# moto.net
KiCad netlist of a schematic drawn in Altium Designer
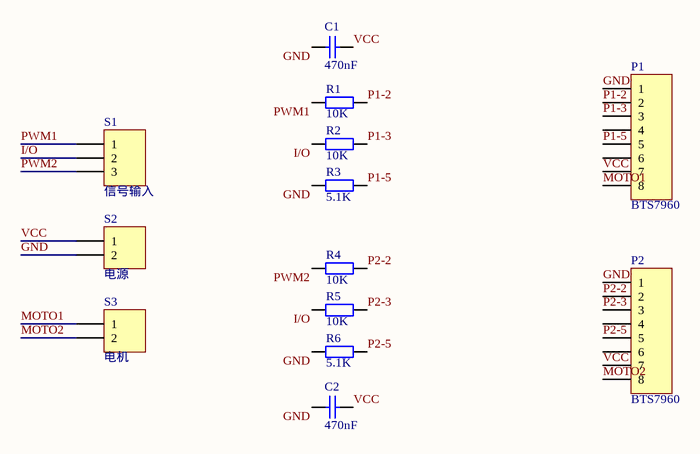
[diagram p0: moto.SchDoc]

(export (version "E")
  (design (tool "Eeschema 10.0.6"))
  (components
    (comp (ref "C1")
      (value "470nF")
      (footprint "0805")
      (description "Capacitor")
      (fields (field (name "PUBLISHER") "Altium Limited"))
      (libsource (lib "Miscellaneous Devices") (part "Cap"))
    )
    (comp (ref "C2")
      (value "470nF")
      (footprint "0805")
      (description "Capacitor")
      (fields (field (name "PUBLISHER") "Altium Limited"))
      (libsource (lib "Miscellaneous Devices") (part "Cap"))
    )
    (comp (ref "P1")
      (value "BTS7960")
      (footprint "BTS7970B")
      (description "Header, 8-Pin")
      (fields (field (name "PUBLISHER") "Altium Limited"))
      (libsource (lib "Miscellaneous Connectors") (part "Header 8"))
    )
    (comp (ref "P2")
      (value "BTS7960")
      (footprint "BTS7970B")
      (description "Header, 8-Pin")
      (fields (field (name "PUBLISHER") "Altium Limited"))
      (libsource (lib "Miscellaneous Connectors") (part "Header 8"))
    )
    (comp (ref "R1")
      (value "10K")
      (footprint "0805")
      (description "Resistor")
      (fields (field (name "PUBLISHER") "Altium Limited"))
      (libsource (lib "Miscellaneous Devices") (part "Res2"))
    )
    (comp (ref "R2")
      (value "10K")
      (footprint "0805")
      (description "Resistor")
      (fields (field (name "PUBLISHER") "Altium Limited"))
      (libsource (lib "") (part "Res2_1"))
    )
    (comp (ref "R3")
      (value "5.1K")
      (footprint "0805")
      (description "Resistor")
      (fields (field (name "PUBLISHER") "Altium Limited"))
      (libsource (lib "") (part "Res2_1"))
    )
    (comp (ref "R4")
      (value "10K")
      (footprint "0805")
      (description "Resistor")
      (fields (field (name "PUBLISHER") "Altium Limited"))
      (libsource (lib "Miscellaneous Devices") (part "Res2"))
    )
    (comp (ref "R5")
      (value "10K")
      (footprint "0805")
      (description "Resistor")
      (fields (field (name "PUBLISHER") "Altium Limited"))
      (libsource (lib "") (part "Res2_1"))
    )
    (comp (ref "R6")
      (value "5.1K")
      (footprint "0805")
      (description "Resistor")
      (fields (field (name "PUBLISHER") "Altium Limited"))
      (libsource (lib "") (part "Res2_1"))
    )
    (comp (ref "S1")
      (value "信号输入")
      (footprint "HDR1X3")
      (description "Header, 3-Pin")
      (fields (field (name "PUBLISHER") "Altium Limited"))
      (libsource (lib "Miscellaneous Connectors") (part "Header 3"))
    )
    (comp (ref "S2")
      (value "电源")
      (footprint "tongzhu")
      (description "Header, 2-Pin")
      (fields (field (name "PUBLISHER") "Altium Limited"))
      (libsource (lib "Miscellaneous Connectors") (part "Header 2"))
    )
    (comp (ref "S3")
      (value "电机")
      (footprint "tongzhu")
      (description "Header, 2-Pin")
      (fields (field (name "PUBLISHER") "Altium Limited"))
      (libsource (lib "Miscellaneous Connectors") (part "Header 2"))
    )
  )
  (nets
    (net (code "1") (name "/GND") (class "Default")
      (node (ref "C1") (pin "1") (pinfunction "1_1") (pintype "passive"))
      (node (ref "C2") (pin "1") (pinfunction "1_1") (pintype "passive"))
      (node (ref "P1") (pin "1") (pinfunction "1_1") (pintype "passive"))
      (node (ref "P2") (pin "1") (pinfunction "1_1") (pintype "passive"))
      (node (ref "R3") (pin "2") (pinfunction "2_2") (pintype "passive"))
      (node (ref "R6") (pin "2") (pinfunction "2_2") (pintype "passive"))
      (node (ref "S2") (pin "2") (pinfunction "2_2") (pintype "passive"))
    )
    (net (code "2") (name "/I{slash}O") (class "Default")
      (node (ref "R2") (pin "2") (pinfunction "2_2") (pintype "passive"))
      (node (ref "R5") (pin "2") (pinfunction "2_2") (pintype "passive"))
      (node (ref "S1") (pin "2") (pinfunction "2_2") (pintype "passive"))
    )
    (net (code "3") (name "/MOTO1") (class "Default")
      (node (ref "P1") (pin "8") (pinfunction "8_8") (pintype "passive"))
      (node (ref "S3") (pin "1") (pinfunction "1_1") (pintype "passive"))
    )
    (net (code "4") (name "/MOTO2") (class "Default")
      (node (ref "P2") (pin "8") (pinfunction "8_8") (pintype "passive"))
      (node (ref "S3") (pin "2") (pinfunction "2_2") (pintype "passive"))
    )
    (net (code "5") (name "/P1-2") (class "Default")
      (node (ref "P1") (pin "2") (pinfunction "2_2") (pintype "passive"))
      (node (ref "R1") (pin "2") (pinfunction "2_2") (pintype "passive"))
    )
    (net (code "6") (name "/P1-3") (class "Default")
      (node (ref "P1") (pin "3") (pinfunction "3_3") (pintype "passive"))
      (node (ref "R2") (pin "1") (pinfunction "1_1") (pintype "passive"))
    )
    (net (code "7") (name "/P1-5") (class "Default")
      (node (ref "P1") (pin "5") (pinfunction "5_5") (pintype "passive"))
      (node (ref "R3") (pin "1") (pinfunction "1_1") (pintype "passive"))
    )
    (net (code "8") (name "/P2-2") (class "Default")
      (node (ref "P2") (pin "2") (pinfunction "2_2") (pintype "passive"))
      (node (ref "R4") (pin "2") (pinfunction "2_2") (pintype "passive"))
    )
    (net (code "9") (name "/P2-3") (class "Default")
      (node (ref "P2") (pin "3") (pinfunction "3_3") (pintype "passive"))
      (node (ref "R5") (pin "1") (pinfunction "1_1") (pintype "passive"))
    )
    (net (code "10") (name "/P2-5") (class "Default")
      (node (ref "P2") (pin "5") (pinfunction "5_5") (pintype "passive"))
      (node (ref "R6") (pin "1") (pinfunction "1_1") (pintype "passive"))
    )
    (net (code "11") (name "/PWM1") (class "Default")
      (node (ref "R1") (pin "1") (pinfunction "1_1") (pintype "passive"))
      (node (ref "S1") (pin "1") (pinfunction "1_1") (pintype "passive"))
    )
    (net (code "12") (name "/PWM2") (class "Default")
      (node (ref "R4") (pin "1") (pinfunction "1_1") (pintype "passive"))
      (node (ref "S1") (pin "3") (pinfunction "3_3") (pintype "passive"))
    )
    (net (code "13") (name "/VCC") (class "Default")
      (node (ref "C1") (pin "2") (pinfunction "2_2") (pintype "passive"))
      (node (ref "C2") (pin "2") (pinfunction "2_2") (pintype "passive"))
      (node (ref "P1") (pin "7") (pinfunction "7_7") (pintype "passive"))
      (node (ref "P2") (pin "7") (pinfunction "7_7") (pintype "passive"))
      (node (ref "S2") (pin "1") (pinfunction "1_1") (pintype "passive"))
    )
    (net (code "14") (name "unconnected-(P1-Pad4)") (class "Default")
      (node (ref "P1") (pin "4") (pinfunction "4_4") (pintype "passive"))
    )
    (net (code "15") (name "unconnected-(P1-Pad6)") (class "Default")
      (node (ref "P1") (pin "6") (pinfunction "6_6") (pintype "passive"))
    )
    (net (code "16") (name "unconnected-(P2-Pad4)") (class "Default")
      (node (ref "P2") (pin "4") (pinfunction "4_4") (pintype "passive"))
    )
    (net (code "17") (name "unconnected-(P2-Pad6)") (class "Default")
      (node (ref "P2") (pin "6") (pinfunction "6_6") (pintype "passive"))
    )
  )
)
